# sanfrancisco_barometer_rev_B.net
KiCad netlist of a schematic drawn in EAGLE
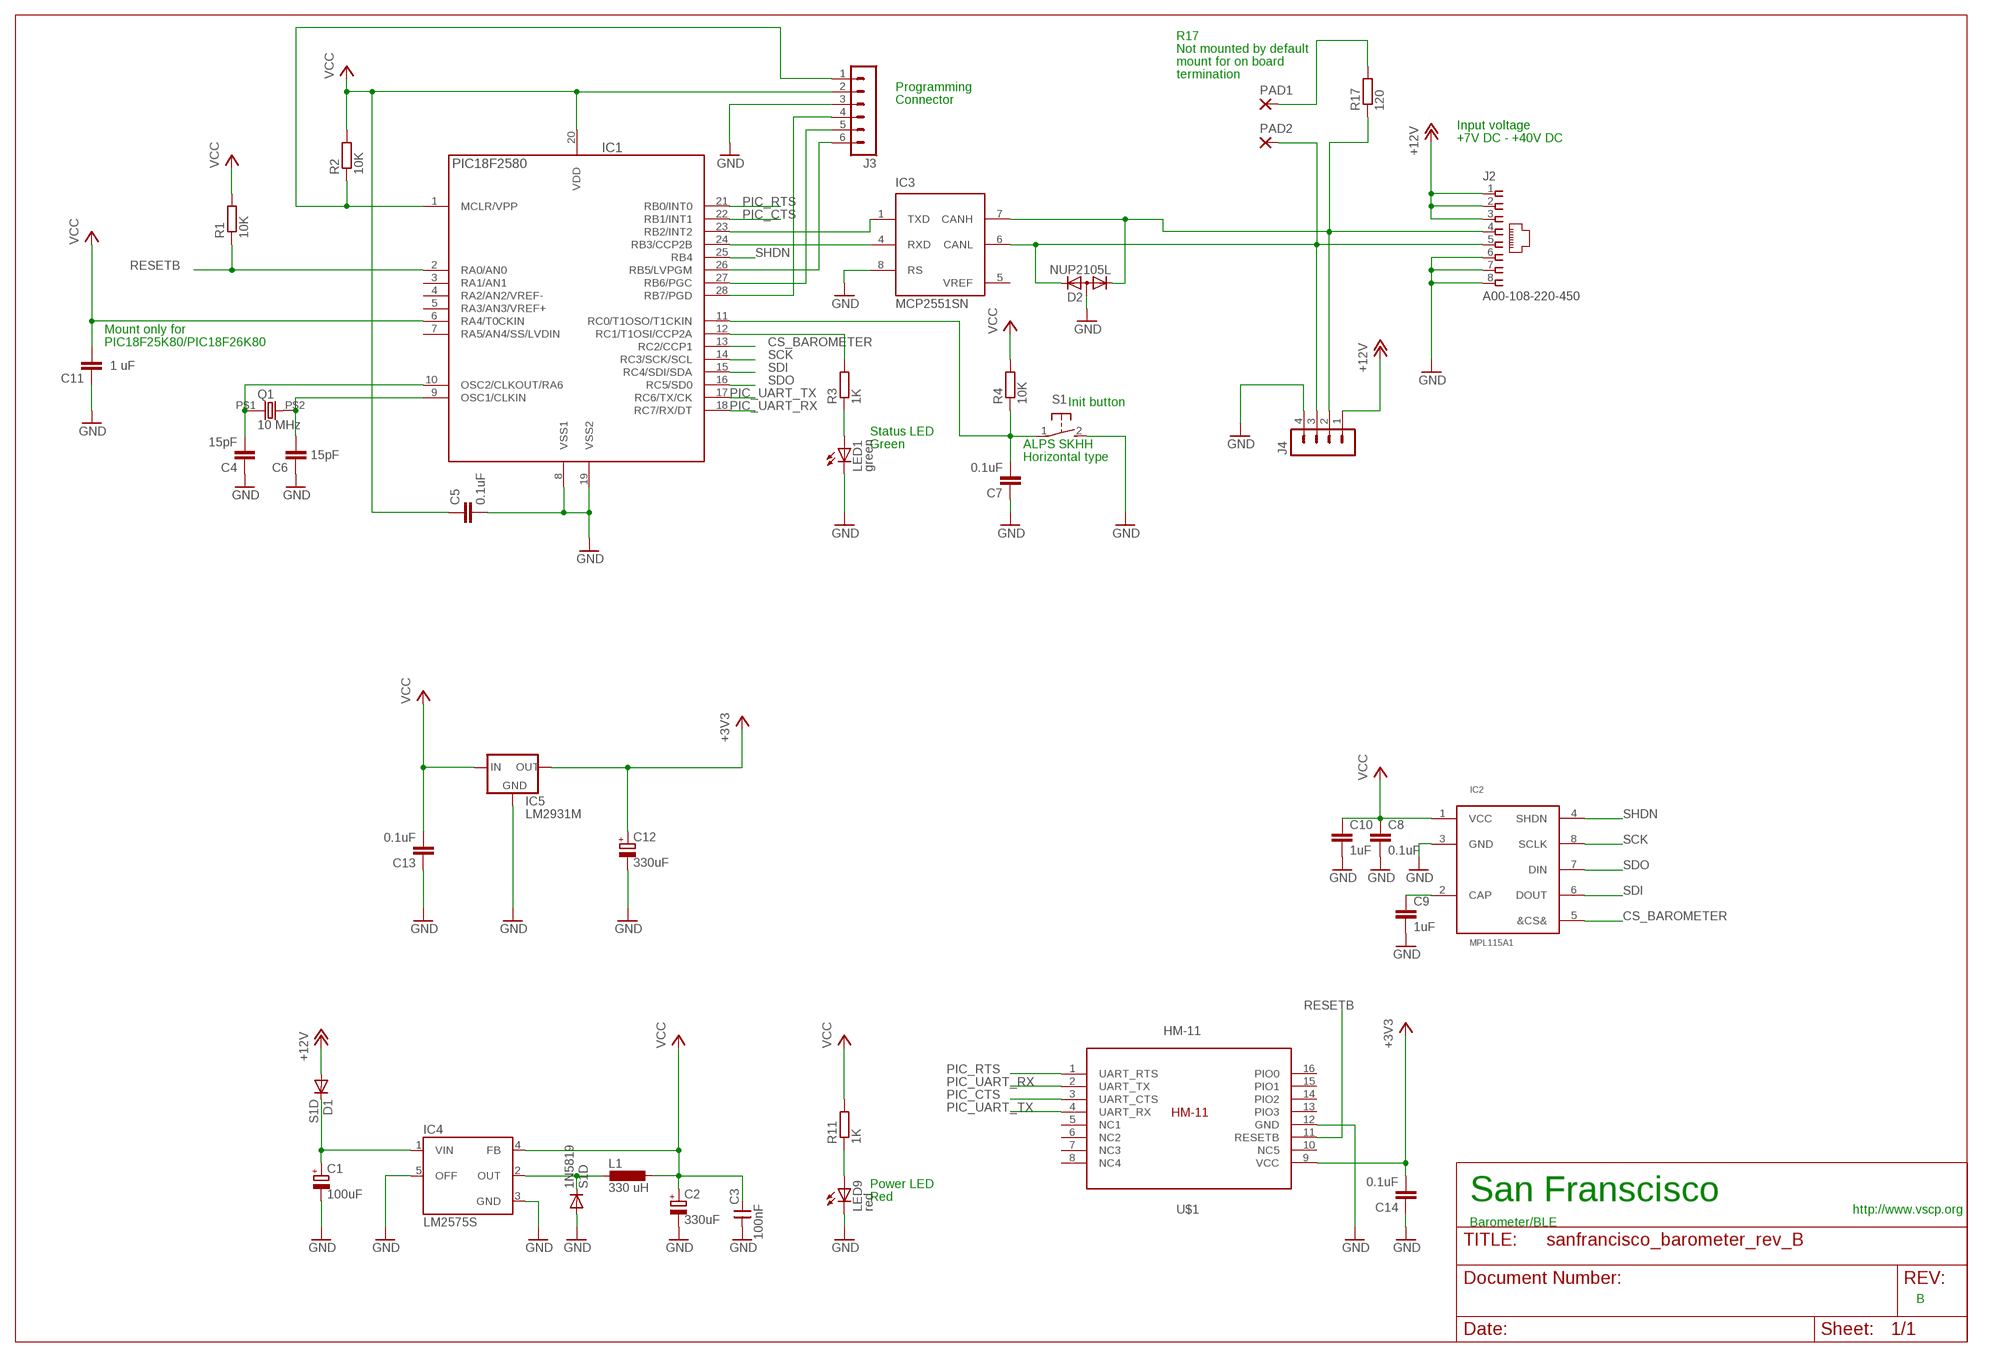
[diagram p0: schematic, sheet 1]

(export (version "E")
  (design (tool "Eeschema 10.0.6"))
  (components
    (comp (ref "1N5819")
      (value "S1D")
      (footprint "eagle-import:SOD123")
      (libsource (lib "eagle-import") (part "DIODE-SOD123"))
    )
    (comp (ref "C1")
      (value "100uF")
      (footprint "eagle-import:PANASONIC_D")
      (libsource (lib "eagle-import") (part "CPOL-EUD"))
    )
    (comp (ref "C2")
      (value "330uF")
      (footprint "eagle-import:PANASONIC_D")
      (libsource (lib "eagle-import") (part "CPOL-EUD"))
    )
    (comp (ref "C3")
      (value "100nF")
      (footprint "eagle-import:0805")
      (libsource (lib "eagle-import") (part "CNP-0805"))
    )
    (comp (ref "C4")
      (value "15pF")
      (footprint "eagle-import:C0805")
      (libsource (lib "eagle-import") (part "C-EUC0805"))
    )
    (comp (ref "C5")
      (value "0.1uF")
      (footprint "eagle-import:C0805")
      (libsource (lib "eagle-import") (part "C-EUC0805"))
    )
    (comp (ref "C6")
      (value "15pF")
      (footprint "eagle-import:C0805")
      (libsource (lib "eagle-import") (part "C-EUC0805"))
    )
    (comp (ref "C7")
      (value "0.1uF")
      (footprint "eagle-import:C0805")
      (libsource (lib "eagle-import") (part "C-EUC0805"))
    )
    (comp (ref "C8")
      (value "0.1uF")
      (footprint "eagle-import:C0805")
      (libsource (lib "eagle-import") (part "C-EUC0805"))
    )
    (comp (ref "C9")
      (value "1uF")
      (footprint "eagle-import:C0805")
      (libsource (lib "eagle-import") (part "C-EUC0805"))
    )
    (comp (ref "C10")
      (value "1uF")
      (footprint "eagle-import:C0805")
      (libsource (lib "eagle-import") (part "C-EUC0805"))
    )
    (comp (ref "C11")
      (value "1 uF")
      (footprint "eagle-import:C0805")
      (libsource (lib "eagle-import") (part "C-EUC0805"))
    )
    (comp (ref "C12")
      (value "330uF")
      (footprint "eagle-import:PANASONIC_D")
      (libsource (lib "eagle-import") (part "CPOL-EUD"))
    )
    (comp (ref "C13")
      (value "0.1uF")
      (footprint "eagle-import:C0805")
      (libsource (lib "eagle-import") (part "C-EUC0805"))
    )
    (comp (ref "C14")
      (value "0.1uF")
      (footprint "eagle-import:C0805")
      (libsource (lib "eagle-import") (part "C-EUC0805"))
    )
    (comp (ref "D1")
      (value "S1D")
      (footprint "eagle-import:SOD123")
      (libsource (lib "eagle-import") (part "DIODE-SOD123"))
    )
    (comp (ref "D2")
      (value "NUP2105L")
      (footprint "eagle-import:SOT23")
      (libsource (lib "eagle-import") (part "DIODE-2CA|ACSOT23"))
    )
    (comp (ref "IC1")
      (value "PIC18F2580")
      (footprint "eagle-import:SO28")
      (libsource (lib "eagle-import") (part "PIC18F252-?I/SOL"))
    )
    (comp (ref "IC2")
      (value "MPL115A1")
      (footprint "eagle-import:LGA8")
      (libsource (lib "eagle-import") (part "MPL115A1"))
    )
    (comp (ref "IC3")
      (value "MCP2551SN")
      (footprint "eagle-import:SO-08")
      (libsource (lib "eagle-import") (part "MCP2551SN"))
    )
    (comp (ref "IC4")
      (value "LM2575S")
      (footprint "eagle-import:TO263-5")
      (libsource (lib "eagle-import") (part "LM2575S"))
    )
    (comp (ref "IC5")
      (value "LM2931M")
      (footprint "eagle-import:SO08")
      (libsource (lib "eagle-import") (part "LM2931M"))
    )
    (comp (ref "J2")
      (value "A00-108-220-450")
      (footprint "eagle-import:RJ-45")
      (libsource (lib "eagle-import") (part "A00-108-220-450"))
    )
    (comp (ref "J3")
      (value "MA06-1")
      (footprint "eagle-import:MA06-1")
      (libsource (lib "eagle-import") (part "MA06-1"))
    )
    (comp (ref "J4")
      (value "MA04-1")
      (footprint "eagle-import:MA04-1")
      (libsource (lib "eagle-import") (part "MA04-1"))
    )
    (comp (ref "L1")
      (value "330 uH")
      (footprint "eagle-import:DO3316P")
      (libsource (lib "eagle-import") (part "DO3316P"))
    )
    (comp (ref "LED1")
      (value "green")
      (footprint "eagle-import:CHIP-LED0805")
      (libsource (lib "eagle-import") (part "LEDCHIP-LED0805"))
    )
    (comp (ref "LED9")
      (value "red")
      (footprint "eagle-import:CHIP-LED0805")
      (libsource (lib "eagle-import") (part "LEDCHIP-LED0805"))
    )
    (comp (ref "PAD1")
      (value "1,6/0,8")
      (footprint "eagle-import:1,6_0,8")
      (libsource (lib "eagle-import") (part "1,6/0,8"))
    )
    (comp (ref "PAD2")
      (value "1,6/0,8")
      (footprint "eagle-import:1,6_0,8")
      (libsource (lib "eagle-import") (part "1,6/0,8"))
    )
    (comp (ref "Q1")
      (value "10 MHz")
      (footprint "eagle-import:9C")
      (libsource (lib "eagle-import") (part "HC-49S"))
    )
    (comp (ref "R1")
      (value "10K")
      (footprint "eagle-import:R0805")
      (libsource (lib "eagle-import") (part "R-EU_R0805"))
    )
    (comp (ref "R2")
      (value "10K")
      (footprint "eagle-import:R0805")
      (libsource (lib "eagle-import") (part "R-EU_R0805"))
    )
    (comp (ref "R3")
      (value "1K")
      (footprint "eagle-import:R0805")
      (libsource (lib "eagle-import") (part "R-EU_R0805"))
    )
    (comp (ref "R4")
      (value "10K")
      (footprint "eagle-import:R0805")
      (libsource (lib "eagle-import") (part "R-EU_R0805"))
    )
    (comp (ref "R11")
      (value "1K")
      (footprint "eagle-import:R0805")
      (libsource (lib "eagle-import") (part "R-EU_R0805"))
    )
    (comp (ref "R17")
      (value "120")
      (footprint "eagle-import:R0805")
      (libsource (lib "eagle-import") (part "R-EU_R0805"))
    )
    (comp (ref "S1")
      (value "31-XX")
      (footprint "eagle-import:B3F-31XX")
      (fields (field (name "MPN") "B3F-3100"))
      (libsource (lib "eagle-import") (part "31-XX"))
    )
    (comp (ref "U$1")
      (value "HM-11")
      (footprint "eagle-import:HM-11")
      (libsource (lib "eagle-import") (part "HM-11"))
    )
  )
  (nets
    (net (code "1") (name "+3V3") (class "Default")
      (node (ref "C12") (pin "+") (pinfunction "+_+") (pintype "passive"))
      (node (ref "C14") (pin "2") (pinfunction "2_2") (pintype "passive"))
      (node (ref "IC5") (pin "1") (pinfunction "OUT_1") (pintype "passive"))
      (node (ref "U$1") (pin "9") (pinfunction "VCC_9") (pintype "power_in"))
    )
    (net (code "2") (name "+12V") (class "Default")
      (node (ref "D1") (pin "A") (pinfunction "A_A") (pintype "passive"))
      (node (ref "J2") (pin "1") (pinfunction "1_1") (pintype "passive"))
      (node (ref "J2") (pin "2") (pinfunction "2_2") (pintype "passive"))
      (node (ref "J2") (pin "3") (pinfunction "3_3") (pintype "passive"))
      (node (ref "J4") (pin "1") (pinfunction "1_1") (pintype "passive"))
    )
    (net (code "3") (name "/CS_BAROMETER") (class "Default")
      (node (ref "IC1") (pin "13") (pinfunction "RC2/CCP1_13") (pintype "bidirectional"))
      (node (ref "IC2") (pin "5") (pinfunction "&CS&_5") (pintype "input"))
    )
    (net (code "4") (name "/PIC_CTS") (class "Default")
      (node (ref "IC1") (pin "22") (pinfunction "RB1/INT1_22") (pintype "bidirectional"))
      (node (ref "U$1") (pin "3") (pinfunction "UART_CTS_3") (pintype "bidirectional"))
    )
    (net (code "5") (name "/PIC_RTS") (class "Default")
      (node (ref "IC1") (pin "21") (pinfunction "RB0/INT0_21") (pintype "bidirectional"))
      (node (ref "U$1") (pin "1") (pinfunction "UART_RTS_1") (pintype "bidirectional"))
    )
    (net (code "6") (name "/PIC_UART_RX") (class "Default")
      (node (ref "IC1") (pin "18") (pinfunction "RC7/RX/DT_18") (pintype "bidirectional"))
      (node (ref "U$1") (pin "2") (pinfunction "UART_TX_2") (pintype "bidirectional"))
    )
    (net (code "7") (name "/PIC_UART_TX") (class "Default")
      (node (ref "IC1") (pin "17") (pinfunction "RC6/TX/CK_17") (pintype "bidirectional"))
      (node (ref "U$1") (pin "4") (pinfunction "UART_RX_4") (pintype "bidirectional"))
    )
    (net (code "8") (name "/RESETB") (class "Default")
      (node (ref "IC1") (pin "2") (pinfunction "RA0/AN0_2") (pintype "bidirectional"))
      (node (ref "R1") (pin "1") (pinfunction "1_1") (pintype "passive"))
      (node (ref "U$1") (pin "11") (pinfunction "RESETB_11") (pintype "bidirectional"))
    )
    (net (code "9") (name "/SCK") (class "Default")
      (node (ref "IC1") (pin "14") (pinfunction "RC3/SCK/SCL_14") (pintype "bidirectional"))
      (node (ref "IC2") (pin "8") (pinfunction "SCLK_8") (pintype "input"))
    )
    (net (code "10") (name "/SDI") (class "Default")
      (node (ref "IC1") (pin "15") (pinfunction "RC4/SDI/SDA_15") (pintype "bidirectional"))
      (node (ref "IC2") (pin "6") (pinfunction "DOUT_6") (pintype "output"))
    )
    (net (code "11") (name "/SDO") (class "Default")
      (node (ref "IC1") (pin "16") (pinfunction "RC5/SD0_16") (pintype "bidirectional"))
      (node (ref "IC2") (pin "7") (pinfunction "DIN_7") (pintype "input"))
    )
    (net (code "12") (name "/SHDN") (class "Default")
      (node (ref "IC1") (pin "25") (pinfunction "RB4_25") (pintype "bidirectional"))
      (node (ref "IC2") (pin "4") (pinfunction "SHDN_4") (pintype "input"))
    )
    (net (code "13") (name "/VREF") (class "Default")
      (node (ref "IC3") (pin "5") (pinfunction "VREF_5") (pintype "power_in"))
    )
    (net (code "14") (name "GND") (class "Default")
      (node (ref "1N5819") (pin "A") (pinfunction "A_A") (pintype "passive"))
      (node (ref "C1") (pin "-") (pinfunction "-_-") (pintype "passive"))
      (node (ref "C10") (pin "2") (pinfunction "2_2") (pintype "passive"))
      (node (ref "C11") (pin "1") (pinfunction "1_1") (pintype "passive"))
      (node (ref "C12") (pin "-") (pinfunction "-_-") (pintype "passive"))
      (node (ref "C13") (pin "1") (pinfunction "1_1") (pintype "passive"))
      (node (ref "C14") (pin "1") (pinfunction "1_1") (pintype "passive"))
      (node (ref "C2") (pin "-") (pinfunction "-_-") (pintype "passive"))
      (node (ref "C3") (pin "1") (pinfunction "1_1") (pintype "passive"))
      (node (ref "C4") (pin "1") (pinfunction "1_1") (pintype "passive"))
      (node (ref "C5") (pin "2") (pinfunction "2_2") (pintype "passive"))
      (node (ref "C6") (pin "1") (pinfunction "1_1") (pintype "passive"))
      (node (ref "C7") (pin "1") (pinfunction "1_1") (pintype "passive"))
      (node (ref "C8") (pin "2") (pinfunction "2_2") (pintype "passive"))
      (node (ref "C9") (pin "2") (pinfunction "2_2") (pintype "passive"))
      (node (ref "D2") (pin "3") (pinfunction "A_3") (pintype "passive"))
      (node (ref "IC1") (pin "19") (pinfunction "VSS2_19") (pintype "power_in"))
      (node (ref "IC1") (pin "8") (pinfunction "VSS1_8") (pintype "power_in"))
      (node (ref "IC2") (pin "3") (pinfunction "GND_3") (pintype "power_in"))
      (node (ref "IC3") (pin "8") (pinfunction "RS_8") (pintype "input"))
      (node (ref "IC4") (pin "3") (pinfunction "GND_3") (pintype "power_in"))
      (node (ref "IC4") (pin "5") (pinfunction "OFF_5") (pintype "input"))
      (node (ref "IC5") (pin "2") (pinfunction "GND_2") (pintype "input"))
      (node (ref "J2") (pin "6") (pinfunction "6_6") (pintype "passive"))
      (node (ref "J2") (pin "7") (pinfunction "7_7") (pintype "passive"))
      (node (ref "J2") (pin "8") (pinfunction "8_8") (pintype "passive"))
      (node (ref "J3") (pin "3") (pinfunction "3_3") (pintype "passive"))
      (node (ref "J4") (pin "4") (pinfunction "4_4") (pintype "passive"))
      (node (ref "LED1") (pin "C") (pinfunction "C_C") (pintype "passive"))
      (node (ref "LED9") (pin "C") (pinfunction "C_C") (pintype "passive"))
      (node (ref "S1") (pin "2") (pinfunction "S_2") (pintype "passive"))
      (node (ref "U$1") (pin "12") (pinfunction "GND_12") (pintype "power_in"))
    )
    (net (code "15") (name "Net-(D2-K1)") (class "Default")
      (node (ref "D2") (pin "1") (pinfunction "K1_1") (pintype "passive"))
      (node (ref "IC3") (pin "7") (pinfunction "CANH_7") (pintype "bidirectional"))
      (node (ref "J2") (pin "4") (pinfunction "4_4") (pintype "passive"))
      (node (ref "J4") (pin "2") (pinfunction "2_2") (pintype "passive"))
      (node (ref "R17") (pin "1") (pinfunction "1_1") (pintype "passive"))
    )
    (net (code "16") (name "Net-(D2-K2)") (class "Default")
      (node (ref "D2") (pin "2") (pinfunction "K2_2") (pintype "passive"))
      (node (ref "IC3") (pin "6") (pinfunction "CANL_6") (pintype "bidirectional"))
      (node (ref "J2") (pin "5") (pinfunction "5_5") (pintype "passive"))
      (node (ref "J4") (pin "3") (pinfunction "3_3") (pintype "passive"))
      (node (ref "PAD2") (pin "1") (pinfunction "P_1") (pintype "passive"))
    )
    (net (code "17") (name "Net-(IC1-MCLR{slash}VPP)") (class "Default")
      (node (ref "IC1") (pin "1") (pinfunction "MCLR/VPP_1") (pintype "input"))
      (node (ref "J3") (pin "1") (pinfunction "1_1") (pintype "passive"))
      (node (ref "R2") (pin "1") (pinfunction "1_1") (pintype "passive"))
    )
    (net (code "18") (name "Net-(IC1-OSC1{slash}CLKIN)") (class "Default")
      (node (ref "C6") (pin "2") (pinfunction "2_2") (pintype "passive"))
      (node (ref "IC1") (pin "9") (pinfunction "OSC1/CLKIN_9") (pintype "input"))
      (node (ref "Q1") (pin "P$2") (pinfunction "2_P$2") (pintype "passive"))
    )
    (net (code "19") (name "Net-(IC1-OSC2{slash}CLKOUT{slash}RA6)") (class "Default")
      (node (ref "C4") (pin "2") (pinfunction "2_2") (pintype "passive"))
      (node (ref "IC1") (pin "10") (pinfunction "OSC2/CLKOUT/RA6_10") (pintype "output"))
      (node (ref "Q1") (pin "P$1") (pinfunction "1_P$1") (pintype "passive"))
    )
    (net (code "20") (name "Net-(IC1-RB2{slash}INT2)") (class "Default")
      (node (ref "IC1") (pin "23") (pinfunction "RB2/INT2_23") (pintype "bidirectional"))
      (node (ref "IC3") (pin "1") (pinfunction "TXD_1") (pintype "input"))
    )
    (net (code "21") (name "Net-(IC1-RB3{slash}CCP2B)") (class "Default")
      (node (ref "IC1") (pin "24") (pinfunction "RB3/CCP2B_24") (pintype "bidirectional"))
      (node (ref "IC3") (pin "4") (pinfunction "RXD_4") (pintype "output"))
    )
    (net (code "22") (name "Net-(IC1-RB5{slash}LVPGM)") (class "Default")
      (node (ref "IC1") (pin "26") (pinfunction "RB5/LVPGM_26") (pintype "bidirectional"))
      (node (ref "J3") (pin "6") (pinfunction "6_6") (pintype "passive"))
    )
    (net (code "23") (name "Net-(IC1-RB6{slash}PGC)") (class "Default")
      (node (ref "IC1") (pin "27") (pinfunction "RB6/PGC_27") (pintype "bidirectional"))
      (node (ref "J3") (pin "5") (pinfunction "5_5") (pintype "passive"))
    )
    (net (code "24") (name "Net-(IC1-RB7{slash}PGD)") (class "Default")
      (node (ref "IC1") (pin "28") (pinfunction "RB7/PGD_28") (pintype "bidirectional"))
      (node (ref "J3") (pin "4") (pinfunction "4_4") (pintype "passive"))
    )
    (net (code "25") (name "Net-(IC1-RC0{slash}T1OSO{slash}T1CKIN)") (class "Default")
      (node (ref "C7") (pin "2") (pinfunction "2_2") (pintype "passive"))
      (node (ref "IC1") (pin "11") (pinfunction "RC0/T1OSO/T1CKIN_11") (pintype "bidirectional"))
      (node (ref "R4") (pin "1") (pinfunction "1_1") (pintype "passive"))
      (node (ref "S1") (pin "1") (pinfunction "P_1") (pintype "passive"))
    )
    (net (code "26") (name "Net-(IC1-RC1{slash}T1OSI{slash}CCP2A)") (class "Default")
      (node (ref "IC1") (pin "12") (pinfunction "RC1/T1OSI/CCP2A_12") (pintype "bidirectional"))
      (node (ref "R3") (pin "2") (pinfunction "2_2") (pintype "passive"))
    )
    (net (code "27") (name "Net-(IC2-CAP)") (class "Default")
      (node (ref "C9") (pin "1") (pinfunction "1_1") (pintype "passive"))
      (node (ref "IC2") (pin "2") (pinfunction "CAP_2") (pintype "power_in"))
    )
    (net (code "28") (name "Net-(IC4-OUT)") (class "Default")
      (node (ref "1N5819") (pin "C") (pinfunction "C_C") (pintype "passive"))
      (node (ref "IC4") (pin "2") (pinfunction "OUT_2") (pintype "output"))
      (node (ref "L1") (pin "1") (pinfunction "1_1") (pintype "passive"))
    )
    (net (code "29") (name "Net-(IC4-VIN)") (class "Default")
      (node (ref "C1") (pin "+") (pinfunction "+_+") (pintype "passive"))
      (node (ref "D1") (pin "C") (pinfunction "C_C") (pintype "passive"))
      (node (ref "IC4") (pin "1") (pinfunction "VIN_1") (pintype "power_in"))
    )
    (net (code "30") (name "Net-(LED1-PadA)") (class "Default")
      (node (ref "LED1") (pin "A") (pinfunction "A_A") (pintype "passive"))
      (node (ref "R3") (pin "1") (pinfunction "1_1") (pintype "passive"))
    )
    (net (code "31") (name "Net-(LED9-PadA)") (class "Default")
      (node (ref "LED9") (pin "A") (pinfunction "A_A") (pintype "passive"))
      (node (ref "R11") (pin "1") (pinfunction "1_1") (pintype "passive"))
    )
    (net (code "32") (name "Net-(PAD1-P)") (class "Default")
      (node (ref "PAD1") (pin "1") (pinfunction "P_1") (pintype "passive"))
      (node (ref "R17") (pin "2") (pinfunction "2_2") (pintype "passive"))
    )
    (net (code "33") (name "VCC") (class "Default")
      (node (ref "C10") (pin "1") (pinfunction "1_1") (pintype "passive"))
      (node (ref "C11") (pin "2") (pinfunction "2_2") (pintype "passive"))
      (node (ref "C13") (pin "2") (pinfunction "2_2") (pintype "passive"))
      (node (ref "C2") (pin "+") (pinfunction "+_+") (pintype "passive"))
      (node (ref "C3") (pin "2") (pinfunction "2_2") (pintype "passive"))
      (node (ref "C5") (pin "1") (pinfunction "1_1") (pintype "passive"))
      (node (ref "C8") (pin "1") (pinfunction "1_1") (pintype "passive"))
      (node (ref "IC1") (pin "20") (pinfunction "VDD_20") (pintype "power_in"))
      (node (ref "IC1") (pin "6") (pinfunction "RA4/T0CKIN_6") (pintype "open_collector"))
      (node (ref "IC2") (pin "1") (pinfunction "VCC_1") (pintype "power_in"))
      (node (ref "IC4") (pin "4") (pinfunction "FB_4") (pintype "input"))
      (node (ref "IC5") (pin "8") (pinfunction "IN_8") (pintype "input"))
      (node (ref "J3") (pin "2") (pinfunction "2_2") (pintype "passive"))
      (node (ref "L1") (pin "2") (pinfunction "2_2") (pintype "passive"))
      (node (ref "R1") (pin "2") (pinfunction "2_2") (pintype "passive"))
      (node (ref "R11") (pin "2") (pinfunction "2_2") (pintype "passive"))
      (node (ref "R2") (pin "2") (pinfunction "2_2") (pintype "passive"))
      (node (ref "R4") (pin "2") (pinfunction "2_2") (pintype "passive"))
    )
    (net (code "34") (name "unconnected-(IC1-RA1{slash}AN1-Pad3)") (class "Default")
      (node (ref "IC1") (pin "3") (pinfunction "RA1/AN1_3") (pintype "bidirectional"))
    )
    (net (code "35") (name "unconnected-(IC1-RA2{slash}AN2{slash}VREF--Pad4)") (class "Default")
      (node (ref "IC1") (pin "4") (pinfunction "RA2/AN2/VREF-_4") (pintype "bidirectional"))
    )
    (net (code "36") (name "unconnected-(IC1-RA3{slash}AN3{slash}VREF+-Pad5)") (class "Default")
      (node (ref "IC1") (pin "5") (pinfunction "RA3/AN3/VREF+_5") (pintype "bidirectional"))
    )
    (net (code "37") (name "unconnected-(IC1-RA5{slash}AN4{slash}SS{slash}LVDIN-Pad7)") (class "Default")
      (node (ref "IC1") (pin "7") (pinfunction "RA5/AN4/SS/LVDIN_7") (pintype "bidirectional"))
    )
    (net (code "38") (name "unconnected-(U$1-NC1-Pad5)") (class "Default")
      (node (ref "U$1") (pin "5") (pinfunction "NC1_5") (pintype "no_connect"))
    )
    (net (code "39") (name "unconnected-(U$1-NC2-Pad6)") (class "Default")
      (node (ref "U$1") (pin "6") (pinfunction "NC2_6") (pintype "no_connect"))
    )
    (net (code "40") (name "unconnected-(U$1-NC3-Pad7)") (class "Default")
      (node (ref "U$1") (pin "7") (pinfunction "NC3_7") (pintype "no_connect"))
    )
    (net (code "41") (name "unconnected-(U$1-NC4-Pad8)") (class "Default")
      (node (ref "U$1") (pin "8") (pinfunction "NC4_8") (pintype "no_connect"))
    )
    (net (code "42") (name "unconnected-(U$1-NC5-Pad10)") (class "Default")
      (node (ref "U$1") (pin "10") (pinfunction "NC5_10") (pintype "bidirectional"))
    )
    (net (code "43") (name "unconnected-(U$1-PIO0-Pad16)") (class "Default")
      (node (ref "U$1") (pin "16") (pinfunction "PIO0_16") (pintype "bidirectional"))
    )
    (net (code "44") (name "unconnected-(U$1-PIO1-Pad15)") (class "Default")
      (node (ref "U$1") (pin "15") (pinfunction "PIO1_15") (pintype "bidirectional"))
    )
    (net (code "45") (name "unconnected-(U$1-PIO2-Pad14)") (class "Default")
      (node (ref "U$1") (pin "14") (pinfunction "PIO2_14") (pintype "bidirectional"))
    )
    (net (code "46") (name "unconnected-(U$1-PIO3-Pad13)") (class "Default")
      (node (ref "U$1") (pin "13") (pinfunction "PIO3_13") (pintype "bidirectional"))
    )
  )
)
